# POWER.net
KiCad netlist of a schematic drawn in Altium Designer
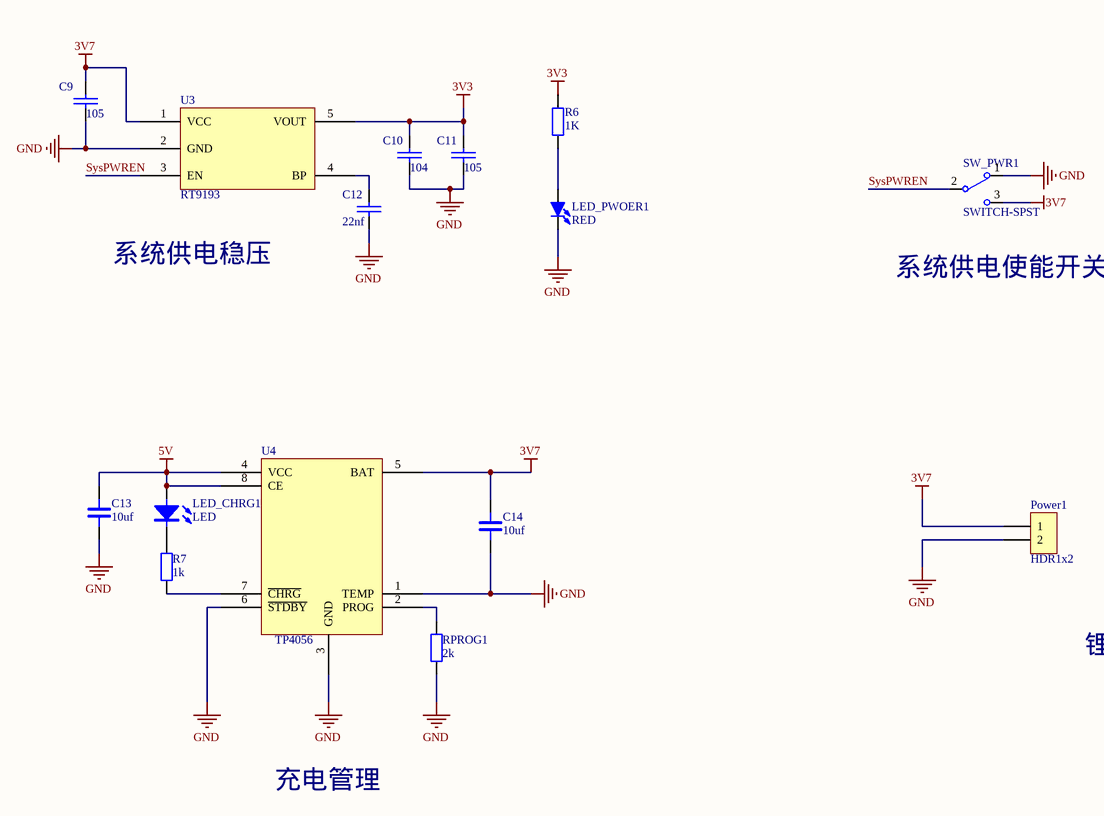
[diagram p0: POWER.SchDoc]

(export (version "E")
  (design (tool "Eeschema 10.0.6"))
  (components
    (comp (ref "C9")
      (value "105")
      (footprint "C 0603_M")
      (description "Capacitor")
      (libsource (lib "*") (part "CAP"))
    )
    (comp (ref "C10")
      (value "104")
      (footprint "C 0603_M")
      (description "Capacitor")
      (libsource (lib "*") (part "CAP"))
    )
    (comp (ref "C11")
      (value "105")
      (footprint "C 0603_M")
      (description "Capacitor")
      (libsource (lib "*") (part "CAP"))
    )
    (comp (ref "C12")
      (value "22nf")
      (footprint "C 0603_M")
      (description "Capacitor")
      (libsource (lib "*") (part "CAP"))
    )
    (comp (ref "C13")
      (value "10uf")
      (footprint "C 0805_M")
      (description "Capacitor")
      (libsource (lib "General") (part "CAP"))
    )
    (comp (ref "C14")
      (value "10uf")
      (footprint "C 0805_M")
      (description "Capacitor")
      (libsource (lib "General") (part "CAP"))
    )
    (comp (ref "LED_CHRG1") (value "LED") (footprint "LED 0603G") (libsource (lib "General") (part "LED")))
    (comp (ref "LED_PWOER1")
      (value "RED")
      (footprint "LED 0603R")
      (description "贴片LED")
      (fields (field (name "版权归属") "源创客"))
      (libsource (lib "9.1   - LED") (part "LED-SMD"))
    )
    (comp (ref "Power1")
      (value "HDR1x2")
      (footprint "XH2.54-LI-2P")
      (description "Connector")
      (libsource (lib "General") (part "HDR1x2"))
    )
    (comp (ref "R6")
      (value "1K")
      (footprint "R 0603_M")
      (description "贴片电阻")
      (fields (field (name "版权归属") "源创客"))
      (libsource (lib "3.1   - 电阻-电容-电感") (part "R"))
    )
    (comp (ref "R7")
      (value "1k")
      (footprint "R 0603_M")
      (description "Resistor")
      (libsource (lib "General") (part "RES"))
    )
    (comp (ref "RPROG1")
      (value "2k")
      (footprint "R 0603_M")
      (description "Resistor")
      (libsource (lib "General") (part "RES"))
    )
    (comp (ref "SW_PWR1")
      (value "SWITCH-SPST")
      (footprint "Switch_3p_2.5mmjianju")
      (description "Switch")
      (libsource (lib "General") (part "SWITCH-SPST"))
    )
    (comp (ref "U3") (value "RT9193") (footprint "SOT-23-5") (libsource (lib "MyLib") (part "RT9193")))
    (comp (ref "U4") (value "TP4056") (footprint "ESOP8") (libsource (lib "MyLib") (part "TP4056")))
  )
  (nets
    (net (code "1") (name "/SysPWREN") (class "Default")
      (node (ref "SW_PWR1") (pin "2") (pinfunction "2_2") (pintype "passive"))
      (node (ref "U3") (pin "3") (pinfunction "EN_3") (pintype "passive"))
    )
    (net (code "2") (name "3V3") (class "Default")
      (node (ref "C10") (pin "1") (pinfunction "1_1") (pintype "passive"))
      (node (ref "C11") (pin "1") (pinfunction "1_1") (pintype "passive"))
      (node (ref "R6") (pin "2") (pinfunction "2_2") (pintype "passive"))
      (node (ref "U3") (pin "5") (pinfunction "VOUT_5") (pintype "passive"))
    )
    (net (code "3") (name "3V7") (class "Default")
      (node (ref "C14") (pin "2") (pinfunction "2_2") (pintype "passive"))
      (node (ref "C9") (pin "1") (pinfunction "1_1") (pintype "passive"))
      (node (ref "Power1") (pin "1") (pinfunction "1_1") (pintype "passive"))
      (node (ref "SW_PWR1") (pin "3") (pinfunction "3_3") (pintype "passive"))
      (node (ref "U3") (pin "1") (pinfunction "VCC_1") (pintype "passive"))
      (node (ref "U4") (pin "5") (pinfunction "BAT_5") (pintype "passive"))
    )
    (net (code "4") (name "5V") (class "Default")
      (node (ref "C13") (pin "2") (pinfunction "2_2") (pintype "passive"))
      (node (ref "LED_CHRG1") (pin "1") (pinfunction "A_1") (pintype "passive"))
      (node (ref "U4") (pin "4") (pinfunction "VCC_4") (pintype "passive"))
      (node (ref "U4") (pin "8") (pinfunction "CE_8") (pintype "passive"))
    )
    (net (code "5") (name "GND") (class "Default")
      (node (ref "C10") (pin "2") (pinfunction "2_2") (pintype "passive"))
      (node (ref "C11") (pin "2") (pinfunction "2_2") (pintype "passive"))
      (node (ref "C12") (pin "2") (pinfunction "2_2") (pintype "passive"))
      (node (ref "C13") (pin "1") (pinfunction "1_1") (pintype "passive"))
      (node (ref "C14") (pin "1") (pinfunction "1_1") (pintype "passive"))
      (node (ref "C9") (pin "2") (pinfunction "2_2") (pintype "passive"))
      (node (ref "LED_PWOER1") (pin "2") (pinfunction "K_2") (pintype "passive"))
      (node (ref "Power1") (pin "2") (pinfunction "2_2") (pintype "passive"))
      (node (ref "RPROG1") (pin "1") (pinfunction "1_1") (pintype "passive"))
      (node (ref "SW_PWR1") (pin "1") (pinfunction "1_1") (pintype "passive"))
      (node (ref "U3") (pin "2") (pinfunction "GND_2") (pintype "passive"))
      (node (ref "U4") (pin "1") (pinfunction "TEMP_1") (pintype "passive"))
      (node (ref "U4") (pin "3") (pinfunction "GND_3") (pintype "passive"))
      (node (ref "U4") (pin "6") (pinfunction "~{STDBY}_6") (pintype "passive"))
    )
    (net (code "6") (name "Net-(LED_CHRG1-C)") (class "Default")
      (node (ref "LED_CHRG1") (pin "2") (pinfunction "C_2") (pintype "passive"))
      (node (ref "R7") (pin "2") (pinfunction "2_2") (pintype "passive"))
    )
    (net (code "7") (name "Net-(LED_PWOER1-A)") (class "Default")
      (node (ref "LED_PWOER1") (pin "1") (pinfunction "A_1") (pintype "passive"))
      (node (ref "R6") (pin "1") (pinfunction "1_1") (pintype "passive"))
    )
    (net (code "8") (name "Net-(U3-BP)") (class "Default")
      (node (ref "C12") (pin "1") (pinfunction "1_1") (pintype "passive"))
      (node (ref "U3") (pin "4") (pinfunction "BP_4") (pintype "passive"))
    )
    (net (code "9") (name "Net-(U4-PROG)") (class "Default")
      (node (ref "RPROG1") (pin "2") (pinfunction "2_2") (pintype "passive"))
      (node (ref "U4") (pin "2") (pinfunction "PROG_2") (pintype "passive"))
    )
    (net (code "10") (name "Net-(U4-~{CHRG})") (class "Default")
      (node (ref "R7") (pin "1") (pinfunction "1_1") (pintype "passive"))
      (node (ref "U4") (pin "7") (pinfunction "~{CHRG}_7") (pintype "passive"))
    )
  )
)
